# fet_overdrive.net
KiCad netlist of a schematic drawn in EAGLE
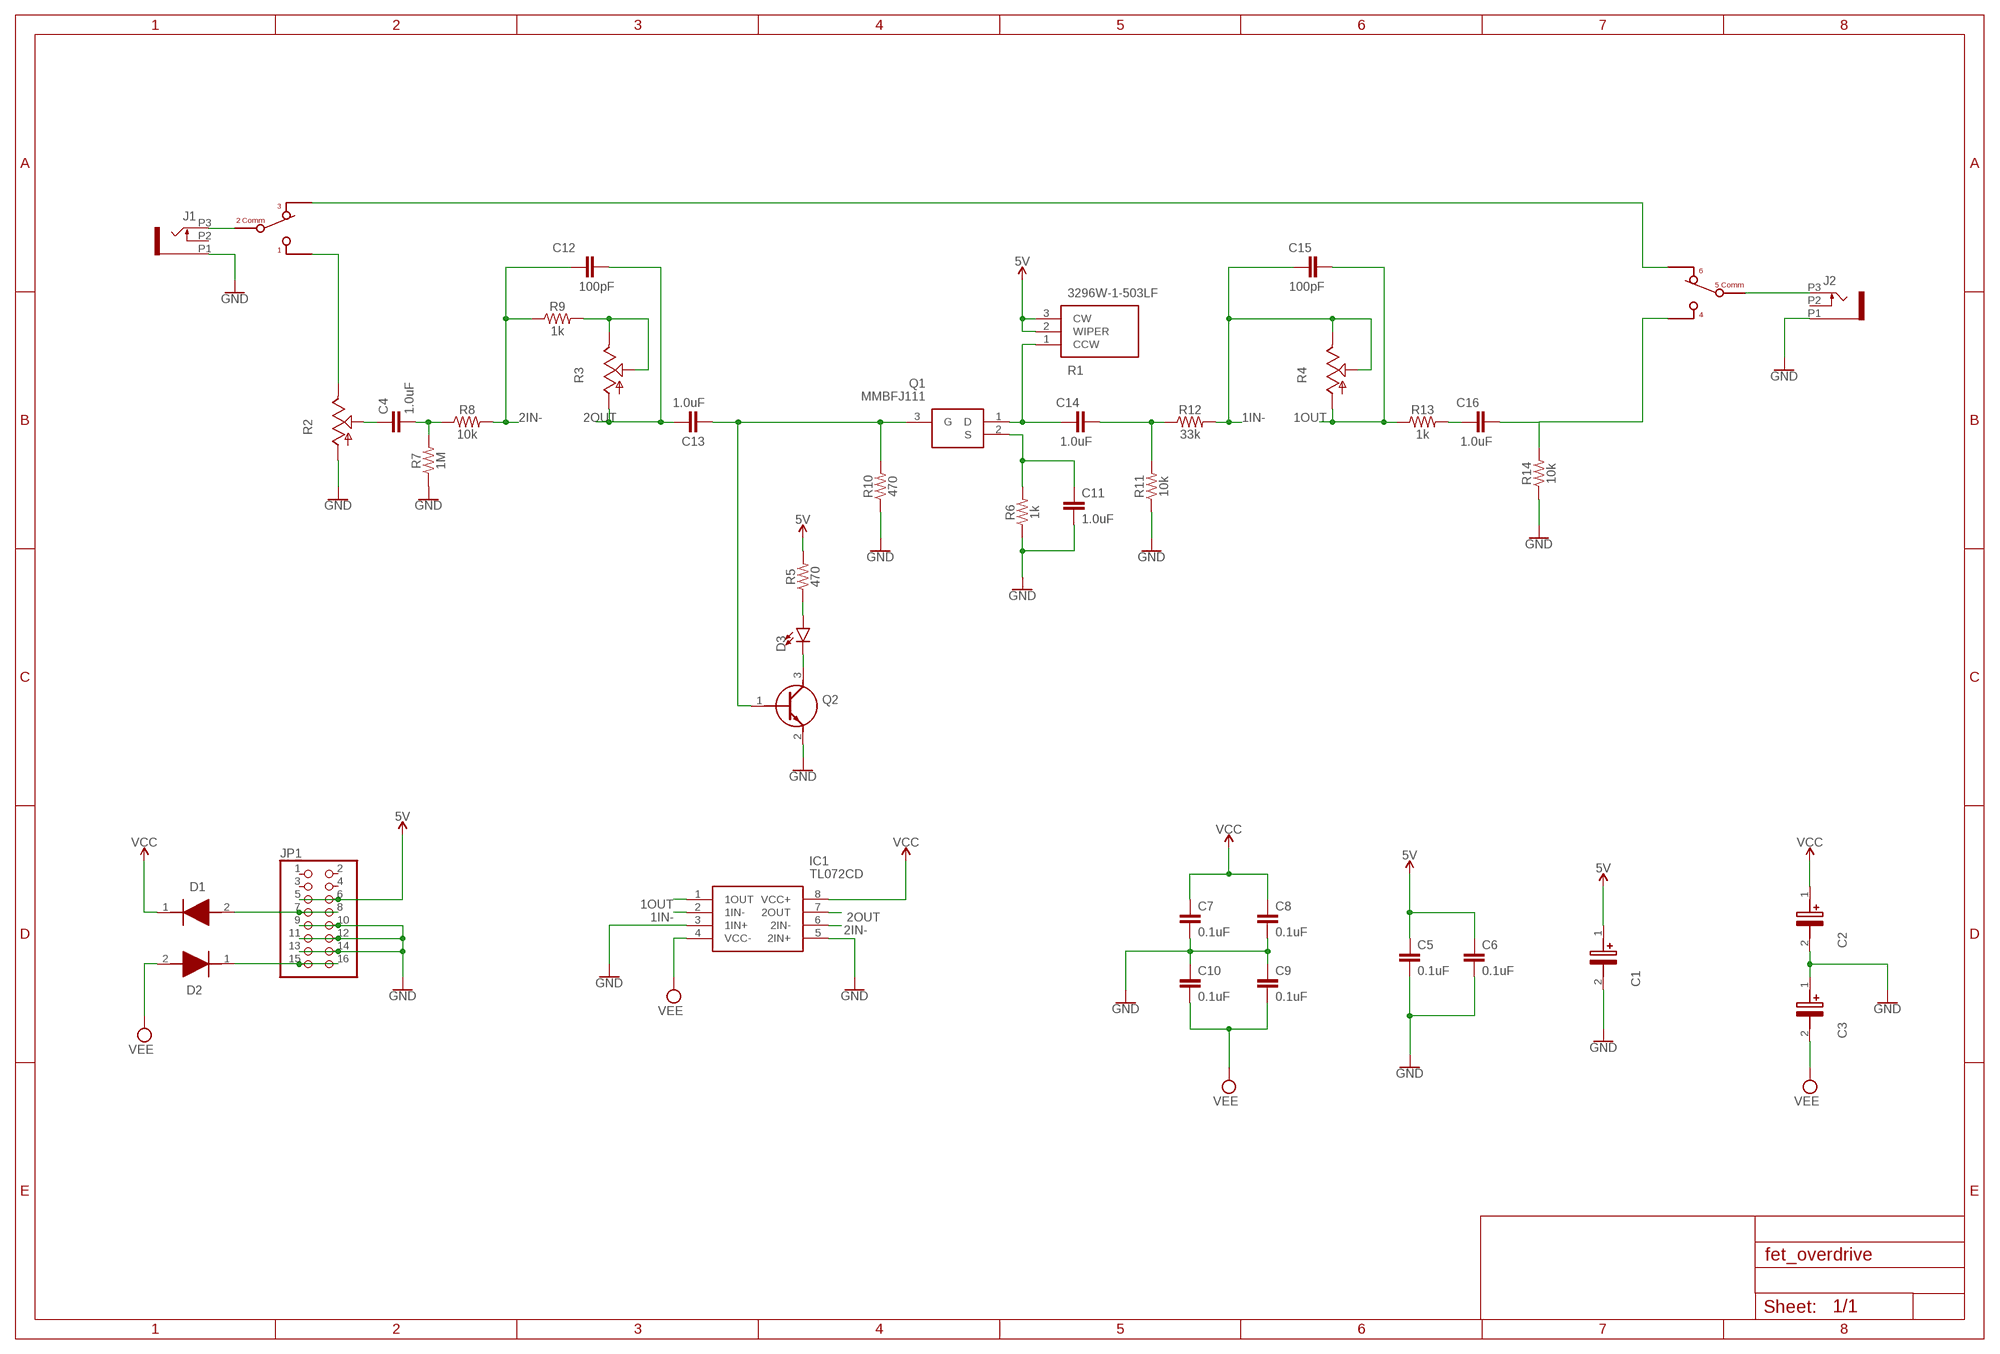
[diagram p0: schematic, sheet 1]

(export (version "E")
  (design (tool "Eeschema 10.0.6"))
  (components
    (comp (ref "C1")
      (value "EEE-FP1E220AR")
      (footprint "eagle-import:EEE0GA101SR")
      (fields (field (name "MOUSER_PART_NUMBER") "667-EEE-FP1E220AR"))
      (libsource (lib "eagle-import") (part "EEE-FP1E220AR"))
    )
    (comp (ref "C2")
      (value "EEE-FK1V470P")
      (footprint "eagle-import:EEE1AA101SP")
      (fields (field (name "MOUSER_PART_NUMBER") "667-EEE-FK1V470P"))
      (libsource (lib "eagle-import") (part "EEE-FK1V470P"))
    )
    (comp (ref "C3")
      (value "EEE-FK1V470P")
      (footprint "eagle-import:EEE1AA101SP")
      (fields (field (name "MOUSER_PART_NUMBER") "667-EEE-FK1V470P"))
      (libsource (lib "eagle-import") (part "EEE-FK1V470P"))
    )
    (comp (ref "C4")
      (value "1.0uF")
      (footprint "eagle-import:0603")
      (libsource (lib "eagle-import") (part "1.0UF-0603-16V-10%"))
    )
    (comp (ref "C5")
      (value "0.1uF")
      (footprint "eagle-import:0603")
      (libsource (lib "eagle-import") (part "0.1UF-0603-100V-10%"))
    )
    (comp (ref "C6")
      (value "0.1uF")
      (footprint "eagle-import:0603")
      (libsource (lib "eagle-import") (part "0.1UF-0603-100V-10%"))
    )
    (comp (ref "C7")
      (value "0.1uF")
      (footprint "eagle-import:0603")
      (libsource (lib "eagle-import") (part "0.1UF-0603-100V-10%"))
    )
    (comp (ref "C8")
      (value "0.1uF")
      (footprint "eagle-import:0603")
      (libsource (lib "eagle-import") (part "0.1UF-0603-100V-10%"))
    )
    (comp (ref "C9")
      (value "0.1uF")
      (footprint "eagle-import:0603")
      (libsource (lib "eagle-import") (part "0.1UF-0603-100V-10%"))
    )
    (comp (ref "C10")
      (value "0.1uF")
      (footprint "eagle-import:0603")
      (libsource (lib "eagle-import") (part "0.1UF-0603-100V-10%"))
    )
    (comp (ref "C11")
      (value "1.0uF")
      (footprint "eagle-import:0603")
      (libsource (lib "eagle-import") (part "1.0UF-0603-16V-10%"))
    )
    (comp (ref "C12")
      (value "100pF")
      (footprint "eagle-import:0603")
      (libsource (lib "eagle-import") (part "100PF-0603-50V-5%"))
    )
    (comp (ref "C13")
      (value "1.0uF")
      (footprint "eagle-import:0603")
      (libsource (lib "eagle-import") (part "1.0UF-0603-16V-10%"))
    )
    (comp (ref "C14")
      (value "1.0uF")
      (footprint "eagle-import:0603")
      (libsource (lib "eagle-import") (part "1.0UF-0603-16V-10%"))
    )
    (comp (ref "C15")
      (value "100pF")
      (footprint "eagle-import:0603")
      (libsource (lib "eagle-import") (part "100PF-0603-50V-5%"))
    )
    (comp (ref "C16")
      (value "1.0uF")
      (footprint "eagle-import:0603")
      (libsource (lib "eagle-import") (part "1.0UF-0603-16V-10%"))
    )
    (comp (ref "D1")
      (value "1N5819HW-7-F")
      (footprint "eagle-import:SOD3716X145N")
      (fields (field (name "MOUSER_PART_NUMBER") "621-1N5819HW-F"))
      (libsource (lib "eagle-import") (part "1N5819HW-7-F"))
    )
    (comp (ref "D2")
      (value "1N5819HW-7-F")
      (footprint "eagle-import:SOD3716X145N")
      (fields (field (name "MOUSER_PART_NUMBER") "621-1N5819HW-F"))
      (libsource (lib "eagle-import") (part "1N5819HW-7-F"))
    )
    (comp (ref "D3")
      (value "LED3MM")
      (footprint "eagle-import:LED_3MM")
      (libsource (lib "eagle-import") (part "LED3MM"))
    )
    (comp (ref "IC1")
      (value "TL072CD")
      (footprint "eagle-import:SOIC127P600X175-8N")
      (fields (field (name "MOUSER_PART_NUMBER") "595-TL072CD"))
      (libsource (lib "eagle-import") (part "TL072CD"))
    )
    (comp (ref "J1")
      (value "PJ301_THONKICONN6")
      (footprint "eagle-import:WQP_PJ_301M6")
      (libsource (lib "eagle-import") (part "PJ301_THONKICONN6"))
    )
    (comp (ref "J2")
      (value "PJ301_THONKICONN6")
      (footprint "eagle-import:WQP_PJ_301M6")
      (libsource (lib "eagle-import") (part "PJ301_THONKICONN6"))
    )
    (comp (ref "JP1")
      (value "PINHD-2X8")
      (footprint "eagle-import:2X08")
      (libsource (lib "eagle-import") (part "PINHD-2X8"))
    )
    (comp (ref "Q1")
      (value "MMBFJ111")
      (footprint "eagle-import:SOT96P237X111-3N")
      (fields (field (name "MOUSER_PART_NUMBER") "512-MMBFJ111"))
      (libsource (lib "eagle-import") (part "MMBFJ111"))
    )
    (comp (ref "Q2")
      (value "SMMBT3904LT1G")
      (footprint "eagle-import:SOT96P237X111-3N")
      (fields (field (name "MOUSER_PART_NUMBER") "863-SMMBT3904LT1G"))
      (libsource (lib "eagle-import") (part "SMMBT3904LT1G"))
    )
    (comp (ref "R1")
      (value "3296W-1-503LF")
      (footprint "eagle-import:3296W-1")
      (fields (field (name "MOUSER_PART_NUMBER") "652-3296W-1-503LF"))
      (libsource (lib "eagle-import") (part "3296W-1-503LF"))
    )
    (comp (ref "R2")
      (value "POT_USVERTICAL_PS")
      (footprint "eagle-import:ALPS_POT_VERTICAL_PS")
      (libsource (lib "eagle-import") (part "POT_USVERTICAL_PS"))
    )
    (comp (ref "R3")
      (value "POT_USVERTICAL_PS")
      (footprint "eagle-import:ALPS_POT_VERTICAL_PS")
      (libsource (lib "eagle-import") (part "POT_USVERTICAL_PS"))
    )
    (comp (ref "R4")
      (value "POT_USVERTICAL_PS")
      (footprint "eagle-import:ALPS_POT_VERTICAL_PS")
      (libsource (lib "eagle-import") (part "POT_USVERTICAL_PS"))
    )
    (comp (ref "R5")
      (value "470")
      (footprint "eagle-import:0603")
      (libsource (lib "eagle-import") (part "470OHM-0603-1/10W-1%"))
    )
    (comp (ref "R6")
      (value "1k")
      (footprint "eagle-import:0603")
      (libsource (lib "eagle-import") (part "1KOHM-0603-1/10W-1%"))
    )
    (comp (ref "R7")
      (value "1M")
      (footprint "eagle-import:0603")
      (libsource (lib "eagle-import") (part "1MOHM-0603-1/4W-5%"))
    )
    (comp (ref "R8")
      (value "10k")
      (footprint "eagle-import:0603")
      (libsource (lib "eagle-import") (part "10KOHM-0603-1/10W-1%"))
    )
    (comp (ref "R9")
      (value "1k")
      (footprint "eagle-import:0603")
      (libsource (lib "eagle-import") (part "1KOHM-0603-1/10W-1%"))
    )
    (comp (ref "R10")
      (value "470")
      (footprint "eagle-import:0603")
      (libsource (lib "eagle-import") (part "470OHM-0603-1/10W-1%"))
    )
    (comp (ref "R11")
      (value "10k")
      (footprint "eagle-import:0603")
      (libsource (lib "eagle-import") (part "10KOHM-0603-1/10W-1%"))
    )
    (comp (ref "R12")
      (value "33k")
      (footprint "eagle-import:0603")
      (libsource (lib "eagle-import") (part "33KOHM-0603-1/10W-1%"))
    )
    (comp (ref "R13")
      (value "1k")
      (footprint "eagle-import:0603")
      (libsource (lib "eagle-import") (part "1KOHM-0603-1/10W-1%"))
    )
    (comp (ref "R14")
      (value "10k")
      (footprint "eagle-import:0603")
      (libsource (lib "eagle-import") (part "10KOHM-0603-1/10W-1%"))
    )
    (comp (ref "U$1")
      (value "DAILYWELL-DPDT")
      (footprint "eagle-import:DAILYWELL-DPDT")
      (libsource (lib "eagle-import") (part "DAILYWELL-DPDT"))
    )
  )
  (nets
    (net (code "1") (name "/1IN-") (class "Default")
      (node (ref "C15") (pin "1") (pinfunction "1_1") (pintype "passive"))
      (node (ref "IC1") (pin "2") (pinfunction "1IN-_2") (pintype "bidirectional"))
      (node (ref "R12") (pin "2") (pinfunction "2_2") (pintype "passive"))
      (node (ref "R4") (pin "P$1") (pinfunction "E_P$1") (pintype "passive"))
      (node (ref "R4") (pin "P$2") (pinfunction "S_P$2") (pintype "passive"))
    )
    (net (code "2") (name "/1OUT") (class "Default")
      (node (ref "C15") (pin "2") (pinfunction "2_2") (pintype "passive"))
      (node (ref "IC1") (pin "1") (pinfunction "1OUT_1") (pintype "bidirectional"))
      (node (ref "R13") (pin "1") (pinfunction "1_1") (pintype "passive"))
      (node (ref "R4") (pin "P$3") (pinfunction "A_P$3") (pintype "passive"))
    )
    (net (code "3") (name "/2IN-") (class "Default")
      (node (ref "C12") (pin "1") (pinfunction "1_1") (pintype "passive"))
      (node (ref "IC1") (pin "6") (pinfunction "2IN-_6") (pintype "bidirectional"))
      (node (ref "R8") (pin "2") (pinfunction "2_2") (pintype "passive"))
      (node (ref "R9") (pin "1") (pinfunction "1_1") (pintype "passive"))
    )
    (net (code "4") (name "/2OUT") (class "Default")
      (node (ref "C12") (pin "2") (pinfunction "2_2") (pintype "passive"))
      (node (ref "C13") (pin "1") (pinfunction "1_1") (pintype "passive"))
      (node (ref "IC1") (pin "7") (pinfunction "2OUT_7") (pintype "bidirectional"))
      (node (ref "R3") (pin "P$3") (pinfunction "A_P$3") (pintype "passive"))
    )
    (net (code "5") (name "5V") (class "Default")
      (node (ref "C1") (pin "1") (pinfunction "+_1") (pintype "bidirectional"))
      (node (ref "C5") (pin "1") (pinfunction "1_1") (pintype "passive"))
      (node (ref "C6") (pin "1") (pinfunction "1_1") (pintype "passive"))
      (node (ref "JP1") (pin "5") (pinfunction "5_5") (pintype "passive"))
      (node (ref "JP1") (pin "6") (pinfunction "6_6") (pintype "passive"))
      (node (ref "R1") (pin "2") (pinfunction "WIPER_2") (pintype "bidirectional"))
      (node (ref "R1") (pin "3") (pinfunction "CW_3") (pintype "bidirectional"))
      (node (ref "R5") (pin "2") (pinfunction "2_2") (pintype "passive"))
    )
    (net (code "6") (name "GND") (class "Default")
      (node (ref "C1") (pin "2") (pinfunction "-_2") (pintype "bidirectional"))
      (node (ref "C10") (pin "1") (pinfunction "1_1") (pintype "passive"))
      (node (ref "C11") (pin "2") (pinfunction "2_2") (pintype "passive"))
      (node (ref "C2") (pin "2") (pinfunction "-_2") (pintype "bidirectional"))
      (node (ref "C3") (pin "1") (pinfunction "+_1") (pintype "bidirectional"))
      (node (ref "C5") (pin "2") (pinfunction "2_2") (pintype "passive"))
      (node (ref "C6") (pin "2") (pinfunction "2_2") (pintype "passive"))
      (node (ref "C7") (pin "2") (pinfunction "2_2") (pintype "passive"))
      (node (ref "C8") (pin "2") (pinfunction "2_2") (pintype "passive"))
      (node (ref "C9") (pin "1") (pinfunction "1_1") (pintype "passive"))
      (node (ref "IC1") (pin "3") (pinfunction "1IN+_3") (pintype "bidirectional"))
      (node (ref "IC1") (pin "5") (pinfunction "2IN+_5") (pintype "bidirectional"))
      (node (ref "J1") (pin "P1") (pinfunction "1_P1") (pintype "passive"))
      (node (ref "J2") (pin "P1") (pinfunction "1_P1") (pintype "passive"))
      (node (ref "JP1") (pin "10") (pinfunction "10_10") (pintype "passive"))
      (node (ref "JP1") (pin "11") (pinfunction "11_11") (pintype "passive"))
      (node (ref "JP1") (pin "12") (pinfunction "12_12") (pintype "passive"))
      (node (ref "JP1") (pin "13") (pinfunction "13_13") (pintype "passive"))
      (node (ref "JP1") (pin "14") (pinfunction "14_14") (pintype "passive"))
      (node (ref "JP1") (pin "9") (pinfunction "9_9") (pintype "passive"))
      (node (ref "Q2") (pin "2") (pinfunction "E_2") (pintype "bidirectional"))
      (node (ref "R10") (pin "1") (pinfunction "1_1") (pintype "passive"))
      (node (ref "R11") (pin "1") (pinfunction "1_1") (pintype "passive"))
      (node (ref "R14") (pin "1") (pinfunction "1_1") (pintype "passive"))
      (node (ref "R2") (pin "P$3") (pinfunction "A_P$3") (pintype "passive"))
      (node (ref "R6") (pin "1") (pinfunction "1_1") (pintype "passive"))
      (node (ref "R7") (pin "1") (pinfunction "1_1") (pintype "passive"))
    )
    (net (code "7") (name "Net-(C4-Pad2)") (class "Default")
      (node (ref "C4") (pin "2") (pinfunction "2_2") (pintype "passive"))
      (node (ref "R7") (pin "2") (pinfunction "2_2") (pintype "passive"))
      (node (ref "R8") (pin "1") (pinfunction "1_1") (pintype "passive"))
    )
    (net (code "8") (name "Net-(C14-Pad2)") (class "Default")
      (node (ref "C14") (pin "2") (pinfunction "2_2") (pintype "passive"))
      (node (ref "R11") (pin "2") (pinfunction "2_2") (pintype "passive"))
      (node (ref "R12") (pin "1") (pinfunction "1_1") (pintype "passive"))
    )
    (net (code "9") (name "Net-(C16-Pad1)") (class "Default")
      (node (ref "C16") (pin "1") (pinfunction "1_1") (pintype "passive"))
      (node (ref "R13") (pin "2") (pinfunction "2_2") (pintype "passive"))
    )
    (net (code "10") (name "Net-(D1-A)") (class "Default")
      (node (ref "D1") (pin "2") (pinfunction "A_2") (pintype "bidirectional"))
      (node (ref "JP1") (pin "7") (pinfunction "7_7") (pintype "passive"))
      (node (ref "JP1") (pin "8") (pinfunction "8_8") (pintype "passive"))
    )
    (net (code "11") (name "Net-(D2-K)") (class "Default")
      (node (ref "D2") (pin "1") (pinfunction "K_1") (pintype "bidirectional"))
      (node (ref "JP1") (pin "15") (pinfunction "15_15") (pintype "passive"))
      (node (ref "JP1") (pin "16") (pinfunction "16_16") (pintype "passive"))
    )
    (net (code "12") (name "Net-(D3-C)") (class "Default")
      (node (ref "D3") (pin "K") (pinfunction "C_K") (pintype "passive"))
      (node (ref "Q2") (pin "3") (pinfunction "C_3") (pintype "bidirectional"))
    )
    (net (code "13") (name "Net-(D3-PadA)") (class "Default")
      (node (ref "D3") (pin "A") (pinfunction "A_A") (pintype "passive"))
      (node (ref "R5") (pin "1") (pinfunction "1_1") (pintype "passive"))
    )
    (net (code "14") (name "Net-(J1-3)") (class "Default")
      (node (ref "J1") (pin "P3") (pinfunction "3_P3") (pintype "passive"))
      (node (ref "U$1") (pin "P$2") (pinfunction "P$2_P$2") (pintype "bidirectional"))
    )
    (net (code "15") (name "Net-(J2-3)") (class "Default")
      (node (ref "J2") (pin "P3") (pinfunction "3_P3") (pintype "passive"))
      (node (ref "U$1") (pin "P$5") (pinfunction "P$2_P$5") (pintype "bidirectional"))
    )
    (net (code "16") (name "Net-(Q1-D)") (class "Default")
      (node (ref "C14") (pin "1") (pinfunction "1_1") (pintype "passive"))
      (node (ref "Q1") (pin "1") (pinfunction "D_1") (pintype "bidirectional"))
      (node (ref "R1") (pin "1") (pinfunction "CCW_1") (pintype "bidirectional"))
    )
    (net (code "17") (name "Net-(Q1-G)") (class "Default")
      (node (ref "C13") (pin "2") (pinfunction "2_2") (pintype "passive"))
      (node (ref "Q1") (pin "3") (pinfunction "G_3") (pintype "bidirectional"))
      (node (ref "Q2") (pin "1") (pinfunction "B_1") (pintype "bidirectional"))
      (node (ref "R10") (pin "2") (pinfunction "2_2") (pintype "passive"))
    )
    (net (code "18") (name "Net-(Q1-S)") (class "Default")
      (node (ref "C11") (pin "1") (pinfunction "1_1") (pintype "passive"))
      (node (ref "Q1") (pin "2") (pinfunction "S_2") (pintype "bidirectional"))
      (node (ref "R6") (pin "2") (pinfunction "2_2") (pintype "passive"))
    )
    (net (code "19") (name "Net-(R2-E)") (class "Default")
      (node (ref "R2") (pin "P$1") (pinfunction "E_P$1") (pintype "passive"))
      (node (ref "U$1") (pin "P$1") (pinfunction "P$1_P$1") (pintype "bidirectional"))
    )
    (net (code "20") (name "Net-(R2-S)") (class "Default")
      (node (ref "C4") (pin "1") (pinfunction "1_1") (pintype "passive"))
      (node (ref "R2") (pin "P$2") (pinfunction "S_P$2") (pintype "passive"))
    )
    (net (code "21") (name "Net-(R3-E)") (class "Default")
      (node (ref "R3") (pin "P$1") (pinfunction "E_P$1") (pintype "passive"))
      (node (ref "R3") (pin "P$2") (pinfunction "S_P$2") (pintype "passive"))
      (node (ref "R9") (pin "2") (pinfunction "2_2") (pintype "passive"))
    )
    (net (code "22") (name "Net-(U$1B-P$1)") (class "Default")
      (node (ref "C16") (pin "2") (pinfunction "2_2") (pintype "passive"))
      (node (ref "R14") (pin "2") (pinfunction "2_2") (pintype "passive"))
      (node (ref "U$1") (pin "P$4") (pinfunction "P$1_P$4") (pintype "bidirectional"))
    )
    (net (code "23") (name "Net-(U$1B-P$3)") (class "Default")
      (node (ref "U$1") (pin "P$3") (pinfunction "P$3_P$3") (pintype "bidirectional"))
      (node (ref "U$1") (pin "P$6") (pinfunction "P$3_P$6") (pintype "bidirectional"))
    )
    (net (code "24") (name "VCC") (class "Default")
      (node (ref "C2") (pin "1") (pinfunction "+_1") (pintype "bidirectional"))
      (node (ref "C7") (pin "1") (pinfunction "1_1") (pintype "passive"))
      (node (ref "C8") (pin "1") (pinfunction "1_1") (pintype "passive"))
      (node (ref "D1") (pin "1") (pinfunction "K_1") (pintype "bidirectional"))
      (node (ref "IC1") (pin "8") (pinfunction "VCC+_8") (pintype "bidirectional"))
    )
    (net (code "25") (name "VEE") (class "Default")
      (node (ref "C10") (pin "2") (pinfunction "2_2") (pintype "passive"))
      (node (ref "C3") (pin "2") (pinfunction "-_2") (pintype "bidirectional"))
      (node (ref "C9") (pin "2") (pinfunction "2_2") (pintype "passive"))
      (node (ref "D2") (pin "2") (pinfunction "A_2") (pintype "bidirectional"))
      (node (ref "IC1") (pin "4") (pinfunction "VCC-_4") (pintype "bidirectional"))
    )
    (net (code "26") (name "unconnected-(J1-2-PadP2)") (class "Default")
      (node (ref "J1") (pin "P2") (pinfunction "2_P2") (pintype "passive"))
    )
    (net (code "27") (name "unconnected-(J2-2-PadP2)") (class "Default")
      (node (ref "J2") (pin "P2") (pinfunction "2_P2") (pintype "passive"))
    )
    (net (code "28") (name "unconnected-(JP1-Pad1)") (class "Default")
      (node (ref "JP1") (pin "1") (pinfunction "1_1") (pintype "passive"))
    )
    (net (code "29") (name "unconnected-(JP1-Pad2)") (class "Default")
      (node (ref "JP1") (pin "2") (pinfunction "2_2") (pintype "passive"))
    )
    (net (code "30") (name "unconnected-(JP1-Pad3)") (class "Default")
      (node (ref "JP1") (pin "3") (pinfunction "3_3") (pintype "passive"))
    )
    (net (code "31") (name "unconnected-(JP1-Pad4)") (class "Default")
      (node (ref "JP1") (pin "4") (pinfunction "4_4") (pintype "passive"))
    )
  )
)
